# jimduino.net
KiCad netlist of a schematic drawn in EAGLE
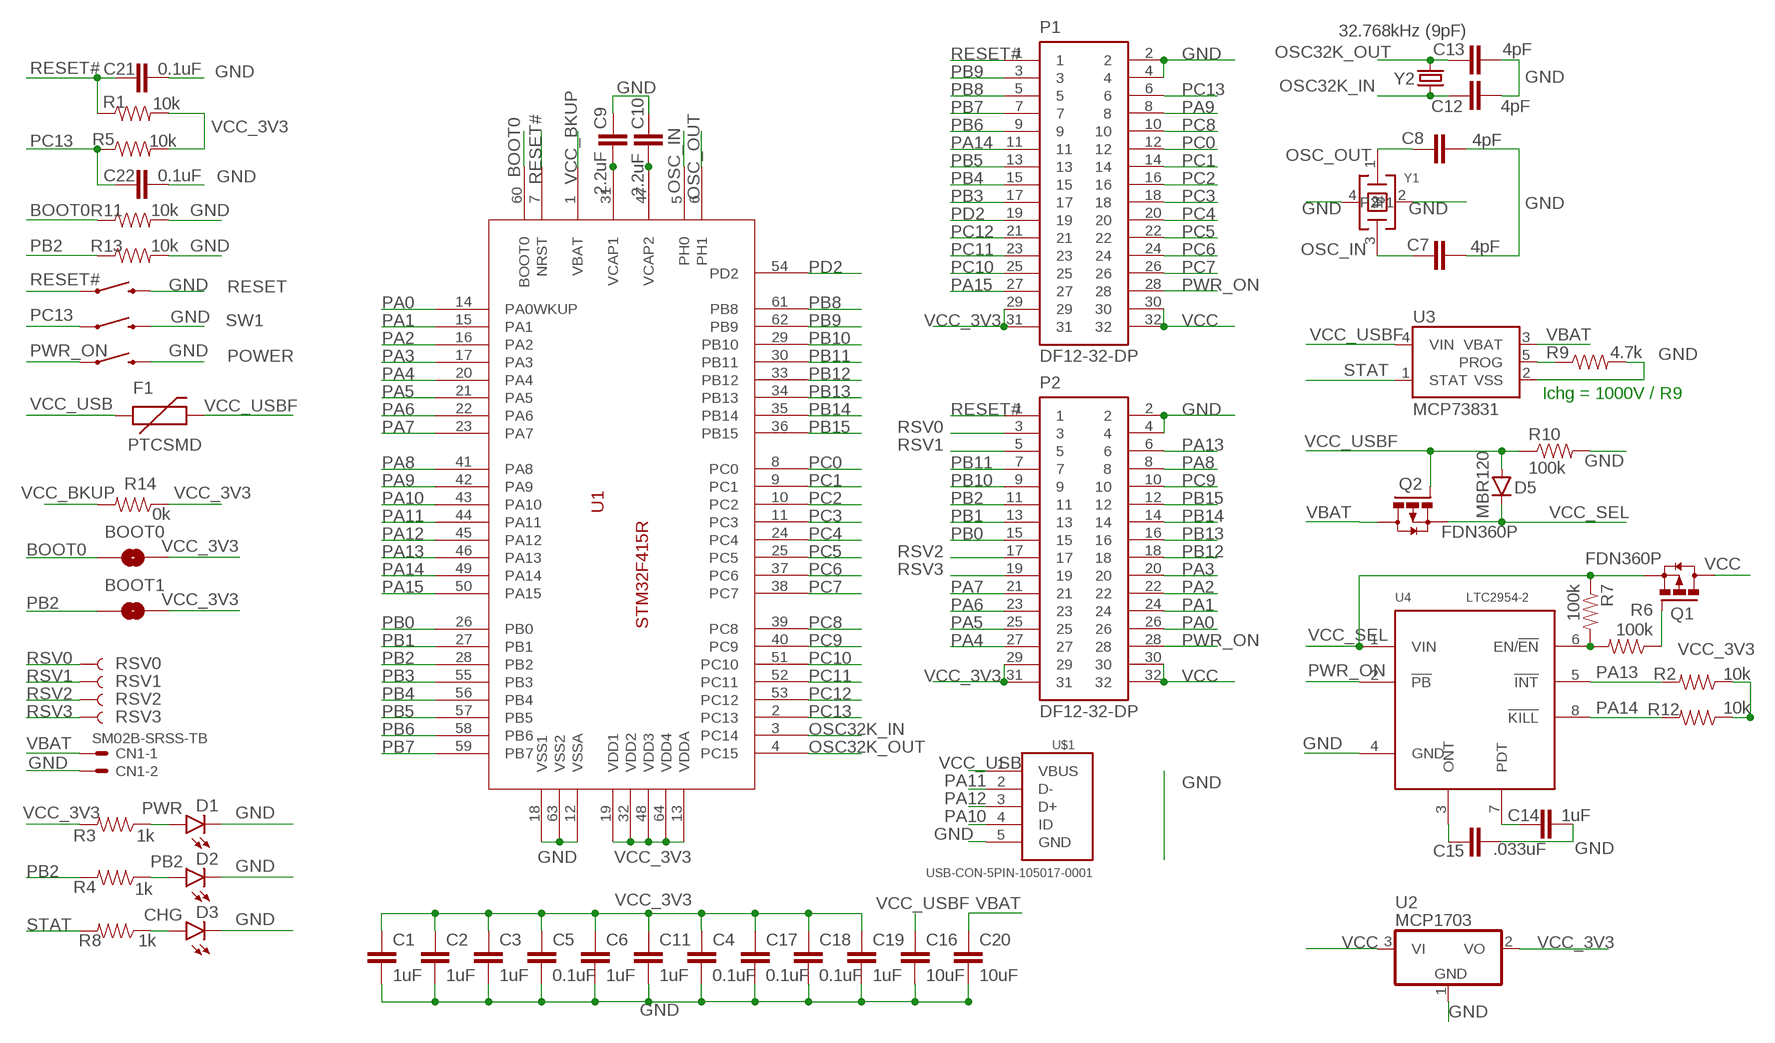
[diagram p0: schematic, sheet 1]

(export (version "E")
  (design (tool "Eeschema 10.0.6"))
  (components
    (comp (ref "BOOT0")
      (value "JUMPER-PAD-2-NOYES_SILK")
      (footprint "eagle-import:PAD-JUMPER-2-NO_YES_SILK")
      (libsource (lib "eagle-import") (part "JUMPER-PAD-2-NOYES_SILK"))
    )
    (comp (ref "BOOT1")
      (value "JUMPER-PAD-2-NOYES_SILK")
      (footprint "eagle-import:PAD-JUMPER-2-NO_YES_SILK")
      (libsource (lib "eagle-import") (part "JUMPER-PAD-2-NOYES_SILK"))
    )
    (comp (ref "C1")
      (value "1uF")
      (footprint "eagle-import:0805")
      (libsource (lib "eagle-import") (part "CAP0805"))
    )
    (comp (ref "C2")
      (value "1uF")
      (footprint "eagle-import:0805")
      (libsource (lib "eagle-import") (part "CAP0805"))
    )
    (comp (ref "C3")
      (value "1uF")
      (footprint "eagle-import:0805")
      (libsource (lib "eagle-import") (part "CAP0805"))
    )
    (comp (ref "C4")
      (value "0.1uF")
      (footprint "eagle-import:0805")
      (libsource (lib "eagle-import") (part "CAP0805"))
    )
    (comp (ref "C5")
      (value "0.1uF")
      (footprint "eagle-import:0805")
      (libsource (lib "eagle-import") (part "CAP0805"))
    )
    (comp (ref "C6")
      (value "1uF")
      (footprint "eagle-import:0805")
      (libsource (lib "eagle-import") (part "CAP0805"))
    )
    (comp (ref "C7")
      (value "4pF")
      (footprint "eagle-import:0805")
      (libsource (lib "eagle-import") (part "CAP0805"))
    )
    (comp (ref "C8")
      (value "4pF")
      (footprint "eagle-import:0805")
      (libsource (lib "eagle-import") (part "CAP0805"))
    )
    (comp (ref "C9")
      (value "2.2uF")
      (footprint "eagle-import:0805")
      (libsource (lib "eagle-import") (part "CAP0805"))
    )
    (comp (ref "C10")
      (value "2.2uF")
      (footprint "eagle-import:0805")
      (libsource (lib "eagle-import") (part "CAP0805"))
    )
    (comp (ref "C11")
      (value "1uF")
      (footprint "eagle-import:0805")
      (libsource (lib "eagle-import") (part "CAP0805"))
    )
    (comp (ref "C12")
      (value "4pF")
      (footprint "eagle-import:0402-CAP")
      (libsource (lib "eagle-import") (part "CAP0402-CAP"))
    )
    (comp (ref "C13")
      (value "4pF")
      (footprint "eagle-import:0402-CAP")
      (libsource (lib "eagle-import") (part "CAP0402-CAP"))
    )
    (comp (ref "C14")
      (value "1uF")
      (footprint "eagle-import:0805")
      (libsource (lib "eagle-import") (part "CAP0805"))
    )
    (comp (ref "C15")
      (value ".033uF")
      (footprint "eagle-import:0805")
      (libsource (lib "eagle-import") (part "CAP0805"))
    )
    (comp (ref "C16")
      (value "10uF")
      (footprint "eagle-import:0805")
      (libsource (lib "eagle-import") (part "CAP0805"))
    )
    (comp (ref "C17")
      (value "0.1uF")
      (footprint "eagle-import:0805")
      (libsource (lib "eagle-import") (part "CAP0805"))
    )
    (comp (ref "C18")
      (value "0.1uF")
      (footprint "eagle-import:0805")
      (libsource (lib "eagle-import") (part "CAP0805"))
    )
    (comp (ref "C19")
      (value "1uF")
      (footprint "eagle-import:0805")
      (libsource (lib "eagle-import") (part "CAP0805"))
    )
    (comp (ref "C20")
      (value "10uF")
      (footprint "eagle-import:0805")
      (libsource (lib "eagle-import") (part "CAP0805"))
    )
    (comp (ref "C21")
      (value "0.1uF")
      (footprint "eagle-import:0805")
      (libsource (lib "eagle-import") (part "CAP0805"))
    )
    (comp (ref "C22")
      (value "0.1uF")
      (footprint "eagle-import:0805")
      (libsource (lib "eagle-import") (part "CAP0805"))
    )
    (comp (ref "CN1")
      (value "SM02B-SRSS-TB")
      (footprint "eagle-import:SM02B-SRSS-TB")
      (libsource (lib "eagle-import") (part "?M02B-SRSS-TBS"))
    )
    (comp (ref "D1")
      (value "PWR")
      (footprint "eagle-import:LED-0603")
      (libsource (lib "eagle-import") (part "LED0603"))
    )
    (comp (ref "D2")
      (value "PB2")
      (footprint "eagle-import:LED-0603")
      (libsource (lib "eagle-import") (part "LED0603"))
    )
    (comp (ref "D3")
      (value "CHG")
      (footprint "eagle-import:LED-0603")
      (libsource (lib "eagle-import") (part "LED0603"))
    )
    (comp (ref "D5")
      (value "MBR120")
      (footprint "eagle-import:SOD-123")
      (libsource (lib "eagle-import") (part "DIODESOD123"))
    )
    (comp (ref "F1")
      (value "PTCSMD")
      (footprint "eagle-import:PTC-1206")
      (libsource (lib "eagle-import") (part "PTCSMD"))
    )
    (comp (ref "P1")
      (value "DF12-32-DP")
      (footprint "eagle-import:DF12-32-DP")
      (fields (field (name "PARTNO") "AS-ITM-00015"))
      (libsource (lib "eagle-import") (part "AS-ITM-00015"))
    )
    (comp (ref "P2")
      (value "DF12-32-DP")
      (footprint "eagle-import:DF12-32-DP")
      (fields (field (name "PARTNO") "AS-ITM-00015"))
      (libsource (lib "eagle-import") (part "AS-ITM-00015"))
    )
    (comp (ref "POWER")
      (value "SWITCH-MOMENTARY-2SMD-REDUNDANT")
      (footprint "eagle-import:TACTILE-SWITCH-SMD")
      (libsource (lib "eagle-import") (part "SWITCH-MOMENTARY-2SMD-REDUNDANT"))
    )
    (comp (ref "Q1")
      (value "FDN360P")
      (footprint "eagle-import:SUPER-SOT3")
      (libsource (lib "eagle-import") (part "FDN360P"))
    )
    (comp (ref "Q2")
      (value "FDN360P")
      (footprint "eagle-import:SUPER-SOT3")
      (libsource (lib "eagle-import") (part "FDN360P"))
    )
    (comp (ref "R1")
      (value "10k")
      (footprint "eagle-import:0805")
      (libsource (lib "eagle-import") (part "RESISTOR0805-RES"))
    )
    (comp (ref "R2")
      (value "10k")
      (footprint "eagle-import:0805")
      (libsource (lib "eagle-import") (part "RESISTOR0805-RES"))
    )
    (comp (ref "R3")
      (value "1k")
      (footprint "eagle-import:0805")
      (libsource (lib "eagle-import") (part "RESISTOR0805-RES"))
    )
    (comp (ref "R4")
      (value "1k")
      (footprint "eagle-import:0805")
      (libsource (lib "eagle-import") (part "RESISTOR0805-RES"))
    )
    (comp (ref "R5")
      (value "10k")
      (footprint "eagle-import:0805")
      (libsource (lib "eagle-import") (part "RESISTOR0805-RES"))
    )
    (comp (ref "R6")
      (value "100k")
      (footprint "eagle-import:0805")
      (libsource (lib "eagle-import") (part "RESISTOR0805-RES"))
    )
    (comp (ref "R7")
      (value "100k")
      (footprint "eagle-import:0805")
      (libsource (lib "eagle-import") (part "RESISTOR0805-RES"))
    )
    (comp (ref "R8")
      (value "1k")
      (footprint "eagle-import:0805")
      (libsource (lib "eagle-import") (part "RESISTOR0805-RES"))
    )
    (comp (ref "R9")
      (value "4.7k")
      (footprint "eagle-import:0805")
      (libsource (lib "eagle-import") (part "RESISTOR0805-RES"))
    )
    (comp (ref "R10")
      (value "100k")
      (footprint "eagle-import:0805")
      (libsource (lib "eagle-import") (part "RESISTOR0805-RES"))
    )
    (comp (ref "R11")
      (value "10k")
      (footprint "eagle-import:0805")
      (libsource (lib "eagle-import") (part "RESISTOR0805-RES"))
    )
    (comp (ref "R12")
      (value "10k")
      (footprint "eagle-import:0805")
      (libsource (lib "eagle-import") (part "RESISTOR0805-RES"))
    )
    (comp (ref "R13")
      (value "10k")
      (footprint "eagle-import:0805")
      (libsource (lib "eagle-import") (part "RESISTOR0805-RES"))
    )
    (comp (ref "R14")
      (value "0k")
      (footprint "eagle-import:0805")
      (libsource (lib "eagle-import") (part "RESISTOR0805-RES"))
    )
    (comp (ref "RESET")
      (value "SWITCH-MOMENTARY-2SMD-REDUNDANT")
      (footprint "eagle-import:TACTILE-SWITCH-SMD")
      (libsource (lib "eagle-import") (part "SWITCH-MOMENTARY-2SMD-REDUNDANT"))
    )
    (comp (ref "RSV0")
      (value "TEST-POINT3")
      (footprint "eagle-import:PAD.03X.03")
      (libsource (lib "eagle-import") (part "TEST-POINT3"))
    )
    (comp (ref "RSV1")
      (value "TEST-POINT3")
      (footprint "eagle-import:PAD.03X.03")
      (libsource (lib "eagle-import") (part "TEST-POINT3"))
    )
    (comp (ref "RSV2")
      (value "TEST-POINT3")
      (footprint "eagle-import:PAD.03X.03")
      (libsource (lib "eagle-import") (part "TEST-POINT3"))
    )
    (comp (ref "RSV3")
      (value "TEST-POINT3")
      (footprint "eagle-import:PAD.03X.03")
      (libsource (lib "eagle-import") (part "TEST-POINT3"))
    )
    (comp (ref "SW1")
      (value "SWITCH-MOMENTARY-2SMD-REDUNDANT")
      (footprint "eagle-import:TACTILE-SWITCH-SMD")
      (libsource (lib "eagle-import") (part "SWITCH-MOMENTARY-2SMD-REDUNDANT"))
    )
    (comp (ref "U$1")
      (value "USB-CON-5PIN-105017-0001")
      (footprint "eagle-import:USB-MICRO-MOLEX-105017-0001")
      (libsource (lib "eagle-import") (part "USB-CON-5PIN-105017-0001"))
    )
    (comp (ref "U1")
      (value "STM32F415R")
      (footprint "eagle-import:LQFP64")
      (libsource (lib "eagle-import") (part "STM32F4R_64PIN_FOXCAR"))
    )
    (comp (ref "U2")
      (value "MCP1703")
      (footprint "eagle-import:SOT23A")
      (libsource (lib "eagle-import") (part "MCP1703"))
    )
    (comp (ref "U3")
      (value "MCP73831")
      (footprint "eagle-import:SOT23-5")
      (libsource (lib "eagle-import") (part "MCP73831"))
    )
    (comp (ref "U4")
      (value "LTC2954-2")
      (footprint "eagle-import:SOT23-8")
      (libsource (lib "eagle-import") (part "LTC2954"))
    )
    (comp (ref "Y1")
      (value "16MHz(9pF)")
      (footprint "eagle-import:ABM11")
      (fields (field (name "PARTNO") "AS-ITM-00228"))
      (libsource (lib "eagle-import") (part "AS-ITM-00228"))
    )
    (comp (ref "Y2")
      (value "32.768kHz (9pF)")
      (footprint "eagle-import:CRYSTAL-32KHZ-SMD_EPSON_MC146")
      (libsource (lib "eagle-import") (part "CRYSTALEPSONMC146"))
    )
  )
  (nets
    (net (code "1") (name "/BOOT0") (class "Default")
      (node (ref "BOOT0") (pin "1") (pinfunction "1_1") (pintype "passive"))
      (node (ref "R11") (pin "1") (pinfunction "1_1") (pintype "passive"))
      (node (ref "U1") (pin "60") (pinfunction "BOOT0_60") (pintype "input"))
    )
    (net (code "2") (name "/GND") (class "Default")
      (node (ref "C1") (pin "2") (pinfunction "2_2") (pintype "passive"))
      (node (ref "C10") (pin "1") (pinfunction "1_1") (pintype "passive"))
      (node (ref "C11") (pin "2") (pinfunction "2_2") (pintype "passive"))
      (node (ref "C12") (pin "2") (pinfunction "2_2") (pintype "passive"))
      (node (ref "C13") (pin "2") (pinfunction "2_2") (pintype "passive"))
      (node (ref "C14") (pin "2") (pinfunction "2_2") (pintype "passive"))
      (node (ref "C15") (pin "2") (pinfunction "2_2") (pintype "passive"))
      (node (ref "C16") (pin "2") (pinfunction "2_2") (pintype "passive"))
      (node (ref "C17") (pin "2") (pinfunction "2_2") (pintype "passive"))
      (node (ref "C18") (pin "2") (pinfunction "2_2") (pintype "passive"))
      (node (ref "C19") (pin "2") (pinfunction "2_2") (pintype "passive"))
      (node (ref "C2") (pin "2") (pinfunction "2_2") (pintype "passive"))
      (node (ref "C20") (pin "2") (pinfunction "2_2") (pintype "passive"))
      (node (ref "C21") (pin "2") (pinfunction "2_2") (pintype "passive"))
      (node (ref "C22") (pin "2") (pinfunction "2_2") (pintype "passive"))
      (node (ref "C3") (pin "2") (pinfunction "2_2") (pintype "passive"))
      (node (ref "C4") (pin "2") (pinfunction "2_2") (pintype "passive"))
      (node (ref "C5") (pin "2") (pinfunction "2_2") (pintype "passive"))
      (node (ref "C6") (pin "2") (pinfunction "2_2") (pintype "passive"))
      (node (ref "C7") (pin "2") (pinfunction "2_2") (pintype "passive"))
      (node (ref "C8") (pin "2") (pinfunction "2_2") (pintype "passive"))
      (node (ref "C9") (pin "1") (pinfunction "1_1") (pintype "passive"))
      (node (ref "CN1") (pin "2") (pinfunction "S_2") (pintype "passive"))
      (node (ref "D1") (pin "C") (pinfunction "C_C") (pintype "passive"))
      (node (ref "D2") (pin "C") (pinfunction "C_C") (pintype "passive"))
      (node (ref "D3") (pin "C") (pinfunction "C_C") (pintype "passive"))
      (node (ref "P1") (pin "2") (pinfunction "2_2") (pintype "bidirectional"))
      (node (ref "P1") (pin "4") (pinfunction "4_4") (pintype "bidirectional"))
      (node (ref "P2") (pin "2") (pinfunction "2_2") (pintype "bidirectional"))
      (node (ref "P2") (pin "4") (pinfunction "4_4") (pintype "bidirectional"))
      (node (ref "POWER") (pin "3") (pinfunction "2_3") (pintype "passive"))
      (node (ref "POWER") (pin "4") (pinfunction "2_4") (pintype "passive"))
      (node (ref "R10") (pin "2") (pinfunction "2_2") (pintype "passive"))
      (node (ref "R11") (pin "2") (pinfunction "2_2") (pintype "passive"))
      (node (ref "R13") (pin "2") (pinfunction "2_2") (pintype "passive"))
      (node (ref "R9") (pin "2") (pinfunction "2_2") (pintype "passive"))
      (node (ref "RESET") (pin "3") (pinfunction "2_3") (pintype "passive"))
      (node (ref "RESET") (pin "4") (pinfunction "2_4") (pintype "passive"))
      (node (ref "SW1") (pin "3") (pinfunction "2_3") (pintype "passive"))
      (node (ref "SW1") (pin "4") (pinfunction "2_4") (pintype "passive"))
      (node (ref "U$1") (pin "5") (pinfunction "GND_5") (pintype "power_in"))
      (node (ref "U1") (pin "12") (pinfunction "VSSA_12") (pintype "input"))
      (node (ref "U1") (pin "18") (pinfunction "VSS1_18") (pintype "input"))
      (node (ref "U1") (pin "63") (pinfunction "VSS2_63") (pintype "input"))
      (node (ref "U2") (pin "1") (pinfunction "GND_1") (pintype "passive"))
      (node (ref "U3") (pin "2") (pinfunction "VSS_2") (pintype "power_in"))
      (node (ref "U4") (pin "4") (pinfunction "GND_4") (pintype "power_in"))
      (node (ref "Y1") (pin "2") (pinfunction "P2_2") (pintype "bidirectional"))
      (node (ref "Y1") (pin "4") (pinfunction "P1_4") (pintype "bidirectional"))
    )
    (net (code "3") (name "/OSC32K_IN") (class "Default")
      (node (ref "C12") (pin "1") (pinfunction "1_1") (pintype "passive"))
      (node (ref "U1") (pin "3") (pinfunction "PC14_3") (pintype "bidirectional"))
      (node (ref "Y2") (pin "P$2") (pinfunction "1_P$2") (pintype "passive"))
    )
    (net (code "4") (name "/OSC32K_OUT") (class "Default")
      (node (ref "C13") (pin "1") (pinfunction "1_1") (pintype "passive"))
      (node (ref "U1") (pin "4") (pinfunction "PC15_4") (pintype "bidirectional"))
      (node (ref "Y2") (pin "P$1") (pinfunction "2_P$1") (pintype "passive"))
    )
    (net (code "5") (name "/OSC_IN") (class "Default")
      (node (ref "C7") (pin "1") (pinfunction "1_1") (pintype "passive"))
      (node (ref "U1") (pin "5") (pinfunction "PH0_5") (pintype "bidirectional"))
      (node (ref "Y1") (pin "3") (pinfunction "2_3") (pintype "bidirectional"))
    )
    (net (code "6") (name "/OSC_OUT") (class "Default")
      (node (ref "C8") (pin "1") (pinfunction "1_1") (pintype "passive"))
      (node (ref "U1") (pin "6") (pinfunction "PH1_6") (pintype "bidirectional"))
      (node (ref "Y1") (pin "1") (pinfunction "1_1") (pintype "bidirectional"))
    )
    (net (code "7") (name "/PA0") (class "Default")
      (node (ref "P2") (pin "26") (pinfunction "26_26") (pintype "bidirectional"))
      (node (ref "U1") (pin "14") (pinfunction "PA0WKUP_14") (pintype "bidirectional"))
    )
    (net (code "8") (name "/PA1") (class "Default")
      (node (ref "P2") (pin "24") (pinfunction "24_24") (pintype "bidirectional"))
      (node (ref "U1") (pin "15") (pinfunction "PA1_15") (pintype "bidirectional"))
    )
    (net (code "9") (name "/PA2") (class "Default")
      (node (ref "P2") (pin "22") (pinfunction "22_22") (pintype "bidirectional"))
      (node (ref "U1") (pin "16") (pinfunction "PA2_16") (pintype "bidirectional"))
    )
    (net (code "10") (name "/PA3") (class "Default")
      (node (ref "P2") (pin "20") (pinfunction "20_20") (pintype "bidirectional"))
      (node (ref "U1") (pin "17") (pinfunction "PA3_17") (pintype "bidirectional"))
    )
    (net (code "11") (name "/PA4") (class "Default")
      (node (ref "P2") (pin "27") (pinfunction "27_27") (pintype "bidirectional"))
      (node (ref "U1") (pin "20") (pinfunction "PA4_20") (pintype "bidirectional"))
    )
    (net (code "12") (name "/PA5") (class "Default")
      (node (ref "P2") (pin "25") (pinfunction "25_25") (pintype "bidirectional"))
      (node (ref "U1") (pin "21") (pinfunction "PA5_21") (pintype "bidirectional"))
    )
    (net (code "13") (name "/PA6") (class "Default")
      (node (ref "P2") (pin "23") (pinfunction "23_23") (pintype "bidirectional"))
      (node (ref "U1") (pin "22") (pinfunction "PA6_22") (pintype "bidirectional"))
    )
    (net (code "14") (name "/PA7") (class "Default")
      (node (ref "P2") (pin "21") (pinfunction "21_21") (pintype "bidirectional"))
      (node (ref "U1") (pin "23") (pinfunction "PA7_23") (pintype "bidirectional"))
    )
    (net (code "15") (name "/PA8") (class "Default")
      (node (ref "P2") (pin "8") (pinfunction "8_8") (pintype "bidirectional"))
      (node (ref "U1") (pin "41") (pinfunction "PA8_41") (pintype "bidirectional"))
    )
    (net (code "16") (name "/PA9") (class "Default")
      (node (ref "P1") (pin "8") (pinfunction "8_8") (pintype "bidirectional"))
      (node (ref "U1") (pin "42") (pinfunction "PA9_42") (pintype "bidirectional"))
    )
    (net (code "17") (name "/PA10") (class "Default")
      (node (ref "U$1") (pin "4") (pinfunction "ID_4") (pintype "bidirectional"))
      (node (ref "U1") (pin "43") (pinfunction "PA10_43") (pintype "bidirectional"))
    )
    (net (code "18") (name "/PA11") (class "Default")
      (node (ref "U$1") (pin "2") (pinfunction "D-_2") (pintype "bidirectional"))
      (node (ref "U1") (pin "44") (pinfunction "PA11_44") (pintype "bidirectional"))
    )
    (net (code "19") (name "/PA12") (class "Default")
      (node (ref "U$1") (pin "3") (pinfunction "D+_3") (pintype "bidirectional"))
      (node (ref "U1") (pin "45") (pinfunction "PA12_45") (pintype "bidirectional"))
    )
    (net (code "20") (name "/PA13") (class "Default")
      (node (ref "P2") (pin "6") (pinfunction "6_6") (pintype "bidirectional"))
      (node (ref "R2") (pin "2") (pinfunction "2_2") (pintype "passive"))
      (node (ref "U1") (pin "46") (pinfunction "PA13_46") (pintype "bidirectional"))
      (node (ref "U4") (pin "5") (pinfunction "~{INT}_5") (pintype "output"))
    )
    (net (code "21") (name "/PA14") (class "Default")
      (node (ref "P1") (pin "11") (pinfunction "11_11") (pintype "bidirectional"))
      (node (ref "R12") (pin "2") (pinfunction "2_2") (pintype "passive"))
      (node (ref "U1") (pin "49") (pinfunction "PA14_49") (pintype "bidirectional"))
      (node (ref "U4") (pin "8") (pinfunction "~{KILL}_8") (pintype "input"))
    )
    (net (code "22") (name "/PA15") (class "Default")
      (node (ref "P1") (pin "27") (pinfunction "27_27") (pintype "bidirectional"))
      (node (ref "U1") (pin "50") (pinfunction "PA15_50") (pintype "bidirectional"))
    )
    (net (code "23") (name "/PB0") (class "Default")
      (node (ref "P2") (pin "15") (pinfunction "15_15") (pintype "bidirectional"))
      (node (ref "U1") (pin "26") (pinfunction "PB0_26") (pintype "bidirectional"))
    )
    (net (code "24") (name "/PB1") (class "Default")
      (node (ref "P2") (pin "13") (pinfunction "13_13") (pintype "bidirectional"))
      (node (ref "U1") (pin "27") (pinfunction "PB1_27") (pintype "bidirectional"))
    )
    (net (code "25") (name "/PB2") (class "Default")
      (node (ref "BOOT1") (pin "1") (pinfunction "1_1") (pintype "passive"))
      (node (ref "P2") (pin "11") (pinfunction "11_11") (pintype "bidirectional"))
      (node (ref "R13") (pin "1") (pinfunction "1_1") (pintype "passive"))
      (node (ref "R4") (pin "2") (pinfunction "2_2") (pintype "passive"))
      (node (ref "U1") (pin "28") (pinfunction "PB2_28") (pintype "bidirectional"))
    )
    (net (code "26") (name "/PB3") (class "Default")
      (node (ref "P1") (pin "17") (pinfunction "17_17") (pintype "bidirectional"))
      (node (ref "U1") (pin "55") (pinfunction "PB3_55") (pintype "bidirectional"))
    )
    (net (code "27") (name "/PB4") (class "Default")
      (node (ref "P1") (pin "15") (pinfunction "15_15") (pintype "bidirectional"))
      (node (ref "U1") (pin "56") (pinfunction "PB4_56") (pintype "bidirectional"))
    )
    (net (code "28") (name "/PB5") (class "Default")
      (node (ref "P1") (pin "13") (pinfunction "13_13") (pintype "bidirectional"))
      (node (ref "U1") (pin "57") (pinfunction "PB5_57") (pintype "bidirectional"))
    )
    (net (code "29") (name "/PB6") (class "Default")
      (node (ref "P1") (pin "9") (pinfunction "9_9") (pintype "bidirectional"))
      (node (ref "U1") (pin "58") (pinfunction "PB6_58") (pintype "bidirectional"))
    )
    (net (code "30") (name "/PB7") (class "Default")
      (node (ref "P1") (pin "7") (pinfunction "7_7") (pintype "bidirectional"))
      (node (ref "U1") (pin "59") (pinfunction "PB7_59") (pintype "bidirectional"))
    )
    (net (code "31") (name "/PB8") (class "Default")
      (node (ref "P1") (pin "5") (pinfunction "5_5") (pintype "bidirectional"))
      (node (ref "U1") (pin "61") (pinfunction "PB8_61") (pintype "bidirectional"))
    )
    (net (code "32") (name "/PB9") (class "Default")
      (node (ref "P1") (pin "3") (pinfunction "3_3") (pintype "bidirectional"))
      (node (ref "U1") (pin "62") (pinfunction "PB9_62") (pintype "bidirectional"))
    )
    (net (code "33") (name "/PB10") (class "Default")
      (node (ref "P2") (pin "9") (pinfunction "9_9") (pintype "bidirectional"))
      (node (ref "U1") (pin "29") (pinfunction "PB10_29") (pintype "bidirectional"))
    )
    (net (code "34") (name "/PB11") (class "Default")
      (node (ref "P2") (pin "7") (pinfunction "7_7") (pintype "bidirectional"))
      (node (ref "U1") (pin "30") (pinfunction "PB11_30") (pintype "bidirectional"))
    )
    (net (code "35") (name "/PB12") (class "Default")
      (node (ref "P2") (pin "18") (pinfunction "18_18") (pintype "bidirectional"))
      (node (ref "U1") (pin "33") (pinfunction "PB12_33") (pintype "bidirectional"))
    )
    (net (code "36") (name "/PB13") (class "Default")
      (node (ref "P2") (pin "16") (pinfunction "16_16") (pintype "bidirectional"))
      (node (ref "U1") (pin "34") (pinfunction "PB13_34") (pintype "bidirectional"))
    )
    (net (code "37") (name "/PB14") (class "Default")
      (node (ref "P2") (pin "14") (pinfunction "14_14") (pintype "bidirectional"))
      (node (ref "U1") (pin "35") (pinfunction "PB14_35") (pintype "bidirectional"))
    )
    (net (code "38") (name "/PB15") (class "Default")
      (node (ref "P2") (pin "12") (pinfunction "12_12") (pintype "bidirectional"))
      (node (ref "U1") (pin "36") (pinfunction "PB15_36") (pintype "bidirectional"))
    )
    (net (code "39") (name "/PC0") (class "Default")
      (node (ref "P1") (pin "12") (pinfunction "12_12") (pintype "bidirectional"))
      (node (ref "U1") (pin "8") (pinfunction "PC0_8") (pintype "bidirectional"))
    )
    (net (code "40") (name "/PC1") (class "Default")
      (node (ref "P1") (pin "14") (pinfunction "14_14") (pintype "bidirectional"))
      (node (ref "U1") (pin "9") (pinfunction "PC1_9") (pintype "bidirectional"))
    )
    (net (code "41") (name "/PC2") (class "Default")
      (node (ref "P1") (pin "16") (pinfunction "16_16") (pintype "bidirectional"))
      (node (ref "U1") (pin "10") (pinfunction "PC2_10") (pintype "bidirectional"))
    )
    (net (code "42") (name "/PC3") (class "Default")
      (node (ref "P1") (pin "18") (pinfunction "18_18") (pintype "bidirectional"))
      (node (ref "U1") (pin "11") (pinfunction "PC3_11") (pintype "bidirectional"))
    )
    (net (code "43") (name "/PC4") (class "Default")
      (node (ref "P1") (pin "20") (pinfunction "20_20") (pintype "bidirectional"))
      (node (ref "U1") (pin "24") (pinfunction "PC4_24") (pintype "bidirectional"))
    )
    (net (code "44") (name "/PC5") (class "Default")
      (node (ref "P1") (pin "22") (pinfunction "22_22") (pintype "bidirectional"))
      (node (ref "U1") (pin "25") (pinfunction "PC5_25") (pintype "bidirectional"))
    )
    (net (code "45") (name "/PC6") (class "Default")
      (node (ref "P1") (pin "24") (pinfunction "24_24") (pintype "bidirectional"))
      (node (ref "U1") (pin "37") (pinfunction "PC6_37") (pintype "bidirectional"))
    )
    (net (code "46") (name "/PC7") (class "Default")
      (node (ref "P1") (pin "26") (pinfunction "26_26") (pintype "bidirectional"))
      (node (ref "U1") (pin "38") (pinfunction "PC7_38") (pintype "bidirectional"))
    )
    (net (code "47") (name "/PC8") (class "Default")
      (node (ref "P1") (pin "10") (pinfunction "10_10") (pintype "bidirectional"))
      (node (ref "U1") (pin "39") (pinfunction "PC8_39") (pintype "bidirectional"))
    )
    (net (code "48") (name "/PC9") (class "Default")
      (node (ref "P2") (pin "10") (pinfunction "10_10") (pintype "bidirectional"))
      (node (ref "U1") (pin "40") (pinfunction "PC9_40") (pintype "bidirectional"))
    )
    (net (code "49") (name "/PC10") (class "Default")
      (node (ref "P1") (pin "25") (pinfunction "25_25") (pintype "bidirectional"))
      (node (ref "U1") (pin "51") (pinfunction "PC10_51") (pintype "bidirectional"))
    )
    (net (code "50") (name "/PC11") (class "Default")
      (node (ref "P1") (pin "23") (pinfunction "23_23") (pintype "bidirectional"))
      (node (ref "U1") (pin "52") (pinfunction "PC11_52") (pintype "bidirectional"))
    )
    (net (code "51") (name "/PC12") (class "Default")
      (node (ref "P1") (pin "21") (pinfunction "21_21") (pintype "bidirectional"))
      (node (ref "U1") (pin "53") (pinfunction "PC12_53") (pintype "bidirectional"))
    )
    (net (code "52") (name "/PC13") (class "Default")
      (node (ref "C22") (pin "1") (pinfunction "1_1") (pintype "passive"))
      (node (ref "P1") (pin "6") (pinfunction "6_6") (pintype "bidirectional"))
      (node (ref "R5") (pin "1") (pinfunction "1_1") (pintype "passive"))
      (node (ref "SW1") (pin "1") (pinfunction "1_1") (pintype "passive"))
      (node (ref "SW1") (pin "2") (pinfunction "1_2") (pintype "passive"))
      (node (ref "U1") (pin "2") (pinfunction "PC13_2") (pintype "bidirectional"))
    )
    (net (code "53") (name "/PD2") (class "Default")
      (node (ref "P1") (pin "19") (pinfunction "19_19") (pintype "bidirectional"))
      (node (ref "U1") (pin "54") (pinfunction "PD2_54") (pintype "bidirectional"))
    )
    (net (code "54") (name "/PWR_ON") (class "Default")
      (node (ref "P1") (pin "28") (pinfunction "28_28") (pintype "bidirectional"))
      (node (ref "P2") (pin "28") (pinfunction "28_28") (pintype "bidirectional"))
      (node (ref "POWER") (pin "1") (pinfunction "1_1") (pintype "passive"))
      (node (ref "POWER") (pin "2") (pinfunction "1_2") (pintype "passive"))
      (node (ref "U4") (pin "2") (pinfunction "~{PB}_2") (pintype "passive"))
    )
    (net (code "55") (name "/RESET#") (class "Default")
      (node (ref "C21") (pin "1") (pinfunction "1_1") (pintype "passive"))
      (node (ref "P1") (pin "1") (pinfunction "1_1") (pintype "bidirectional"))
      (node (ref "P2") (pin "1") (pinfunction "1_1") (pintype "bidirectional"))
      (node (ref "R1") (pin "1") (pinfunction "1_1") (pintype "passive"))
      (node (ref "RESET") (pin "1") (pinfunction "1_1") (pintype "passive"))
      (node (ref "RESET") (pin "2") (pinfunction "1_2") (pintype "passive"))
      (node (ref "U1") (pin "7") (pinfunction "NRST_7") (pintype "input"))
    )
    (net (code "56") (name "/RSV0") (class "Default")
      (node (ref "P2") (pin "3") (pinfunction "3_3") (pintype "bidirectional"))
      (node (ref "RSV0") (pin "P$1") (pinfunction "1_P$1") (pintype "bidirectional"))
    )
    (net (code "57") (name "/RSV1") (class "Default")
      (node (ref "P2") (pin "5") (pinfunction "5_5") (pintype "bidirectional"))
      (node (ref "RSV1") (pin "P$1") (pinfunction "1_P$1") (pintype "bidirectional"))
    )
    (net (code "58") (name "/RSV2") (class "Default")
      (node (ref "P2") (pin "17") (pinfunction "17_17") (pintype "bidirectional"))
      (node (ref "RSV2") (pin "P$1") (pinfunction "1_P$1") (pintype "bidirectional"))
    )
    (net (code "59") (name "/RSV3") (class "Default")
      (node (ref "P2") (pin "19") (pinfunction "19_19") (pintype "bidirectional"))
      (node (ref "RSV3") (pin "P$1") (pinfunction "1_P$1") (pintype "bidirectional"))
    )
    (net (code "60") (name "/STAT") (class "Default")
      (node (ref "R8") (pin "2") (pinfunction "2_2") (pintype "passive"))
      (node (ref "U3") (pin "1") (pinfunction "STAT_1") (pintype "output"))
    )
    (net (code "61") (name "/VBAT") (class "Default")
      (node (ref "C20") (pin "1") (pinfunction "1_1") (pintype "passive"))
      (node (ref "CN1") (pin "1") (pinfunction "S_1") (pintype "passive"))
      (node (ref "Q2") (pin "3") (pinfunction "D_3") (pintype "passive"))
      (node (ref "U3") (pin "3") (pinfunction "VBAT_3") (pintype "power_in"))
    )
    (net (code "62") (name "/VCC") (class "Default")
      (node (ref "P1") (pin "30") (pinfunction "30_30") (pintype "bidirectional"))
      (node (ref "P1") (pin "32") (pinfunction "32_32") (pintype "bidirectional"))
      (node (ref "P2") (pin "30") (pinfunction "30_30") (pintype "bidirectional"))
      (node (ref "P2") (pin "32") (pinfunction "32_32") (pintype "bidirectional"))
      (node (ref "Q1") (pin "3") (pinfunction "D_3") (pintype "passive"))
      (node (ref "U2") (pin "3") (pinfunction "VI_3") (pintype "input"))
    )
    (net (code "63") (name "/VCC_3V3") (class "Default")
      (node (ref "BOOT0") (pin "2") (pinfunction "2_2") (pintype "passive"))
      (node (ref "BOOT1") (pin "2") (pinfunction "2_2") (pintype "passive"))
      (node (ref "C1") (pin "1") (pinfunction "1_1") (pintype "passive"))
      (node (ref "C11") (pin "1") (pinfunction "1_1") (pintype "passive"))
      (node (ref "C17") (pin "1") (pinfunction "1_1") (pintype "passive"))
      (node (ref "C18") (pin "1") (pinfunction "1_1") (pintype "passive"))
      (node (ref "C19") (pin "1") (pinfunction "1_1") (pintype "passive"))
      (node (ref "C2") (pin "1") (pinfunction "1_1") (pintype "passive"))
      (node (ref "C3") (pin "1") (pinfunction "1_1") (pintype "passive"))
      (node (ref "C4") (pin "1") (pinfunction "1_1") (pintype "passive"))
      (node (ref "C5") (pin "1") (pinfunction "1_1") (pintype "passive"))
      (node (ref "C6") (pin "1") (pinfunction "1_1") (pintype "passive"))
      (node (ref "P1") (pin "29") (pinfunction "29_29") (pintype "bidirectional"))
      (node (ref "P1") (pin "31") (pinfunction "31_31") (pintype "bidirectional"))
      (node (ref "P2") (pin "29") (pinfunction "29_29") (pintype "bidirectional"))
      (node (ref "P2") (pin "31") (pinfunction "31_31") (pintype "bidirectional"))
      (node (ref "R1") (pin "2") (pinfunction "2_2") (pintype "passive"))
      (node (ref "R12") (pin "1") (pinfunction "1_1") (pintype "passive"))
      (node (ref "R14") (pin "1") (pinfunction "1_1") (pintype "passive"))
      (node (ref "R2") (pin "1") (pinfunction "1_1") (pintype "passive"))
      (node (ref "R3") (pin "2") (pinfunction "2_2") (pintype "passive"))
      (node (ref "R5") (pin "2") (pinfunction "2_2") (pintype "passive"))
      (node (ref "U1") (pin "13") (pinfunction "VDDA_13") (pintype "power_in"))
      (node (ref "U1") (pin "19") (pinfunction "VDD1_19") (pintype "power_in"))
      (node (ref "U1") (pin "32") (pinfunction "VDD2_32") (pintype "power_in"))
      (node (ref "U1") (pin "48") (pinfunction "VDD3_48") (pintype "power_in"))
      (node (ref "U1") (pin "64") (pinfunction "VDD4_64") (pintype "power_in"))
      (node (ref "U2") (pin "2") (pinfunction "VO_2") (pintype "passive"))
    )
    (net (code "64") (name "/VCC_BKUP") (class "Default")
      (node (ref "R14") (pin "2") (pinfunction "2_2") (pintype "passive"))
      (node (ref "U1") (pin "1") (pinfunction "VBAT_1") (pintype "bidirectional"))
    )
    (net (code "65") (name "/VCC_SEL") (class "Default")
      (node (ref "D5") (pin "C") (pinfunction "C_C") (pintype "passive"))
      (node (ref "Q1") (pin "2") (pinfunction "S_2") (pintype "passive"))
      (node (ref "Q2") (pin "2") (pinfunction "S_2") (pintype "passive"))
      (node (ref "R7") (pin "1") (pinfunction "1_1") (pintype "passive"))
      (node (ref "U4") (pin "1") (pinfunction "VIN_1") (pintype "power_in"))
    )
    (net (code "66") (name "/VCC_USB") (class "Default")
      (node (ref "F1") (pin "1") (pinfunction "1_1") (pintype "bidirectional"))
      (node (ref "U$1") (pin "1") (pinfunction "VBUS_1") (pintype "power_in"))
    )
    (net (code "67") (name "/VCC_USBF") (class "Default")
      (node (ref "C16") (pin "1") (pinfunction "1_1") (pintype "passive"))
      (node (ref "D5") (pin "A") (pinfunction "A_A") (pintype "passive"))
      (node (ref "F1") (pin "2") (pinfunction "2_2") (pintype "bidirectional"))
      (node (ref "Q2") (pin "1") (pinfunction "G_1") (pintype "passive"))
      (node (ref "R10") (pin "1") (pinfunction "1_1") (pintype "passive"))
      (node (ref "U3") (pin "4") (pinfunction "VIN_4") (pintype "power_in"))
    )
    (net (code "68") (name "Net-(D1-PadA)") (class "Default")
      (node (ref "D1") (pin "A") (pinfunction "A_A") (pintype "passive"))
      (node (ref "R3") (pin "1") (pinfunction "1_1") (pintype "passive"))
    )
    (net (code "69") (name "Net-(D2-PadA)") (class "Default")
      (node (ref "D2") (pin "A") (pinfunction "A_A") (pintype "passive"))
      (node (ref "R4") (pin "1") (pinfunction "1_1") (pintype "passive"))
    )
    (net (code "70") (name "Net-(D3-PadA)") (class "Default")
      (node (ref "D3") (pin "A") (pinfunction "A_A") (pintype "passive"))
      (node (ref "R8") (pin "1") (pinfunction "1_1") (pintype "passive"))
    )
    (net (code "71") (name "Net-(Q1-G)") (class "Default")
      (node (ref "Q1") (pin "1") (pinfunction "G_1") (pintype "passive"))
      (node (ref "R6") (pin "1") (pinfunction "1_1") (pintype "passive"))
    )
    (net (code "72") (name "Net-(U1-VCAP1)") (class "Default")
      (node (ref "C9") (pin "2") (pinfunction "2_2") (pintype "passive"))
      (node (ref "U1") (pin "31") (pinfunction "VCAP1_31") (pintype "output"))
    )
    (net (code "73") (name "Net-(U1-VCAP2)") (class "Default")
      (node (ref "C10") (pin "2") (pinfunction "2_2") (pintype "passive"))
      (node (ref "U1") (pin "47") (pinfunction "VCAP2_47") (pintype "output"))
    )
    (net (code "74") (name "Net-(U3-PROG)") (class "Default")
      (node (ref "R9") (pin "1") (pinfunction "1_1") (pintype "passive"))
      (node (ref "U3") (pin "5") (pinfunction "PROG_5") (pintype "input"))
    )
    (net (code "75") (name "Net-(U4-EN{slash}~{EN})") (class "Default")
      (node (ref "R6") (pin "2") (pinfunction "2_2") (pintype "passive"))
      (node (ref "R7") (pin "2") (pinfunction "2_2") (pintype "passive"))
      (node (ref "U4") (pin "6") (pinfunction "EN/~{EN}_6") (pintype "output"))
    )
    (net (code "76") (name "Net-(U4-ONT)") (class "Default")
      (node (ref "C15") (pin "1") (pinfunction "1_1") (pintype "passive"))
      (node (ref "U4") (pin "3") (pinfunction "ONT_3") (pintype "passive"))
    )
    (net (code "77") (name "Net-(U4-PDT)") (class "Default")
      (node (ref "C14") (pin "1") (pinfunction "1_1") (pintype "passive"))
      (node (ref "U4") (pin "7") (pinfunction "PDT_7") (pintype "passive"))
    )
  )
)
